# wakeel125.net
KiCad netlist of a schematic drawn in EAGLE
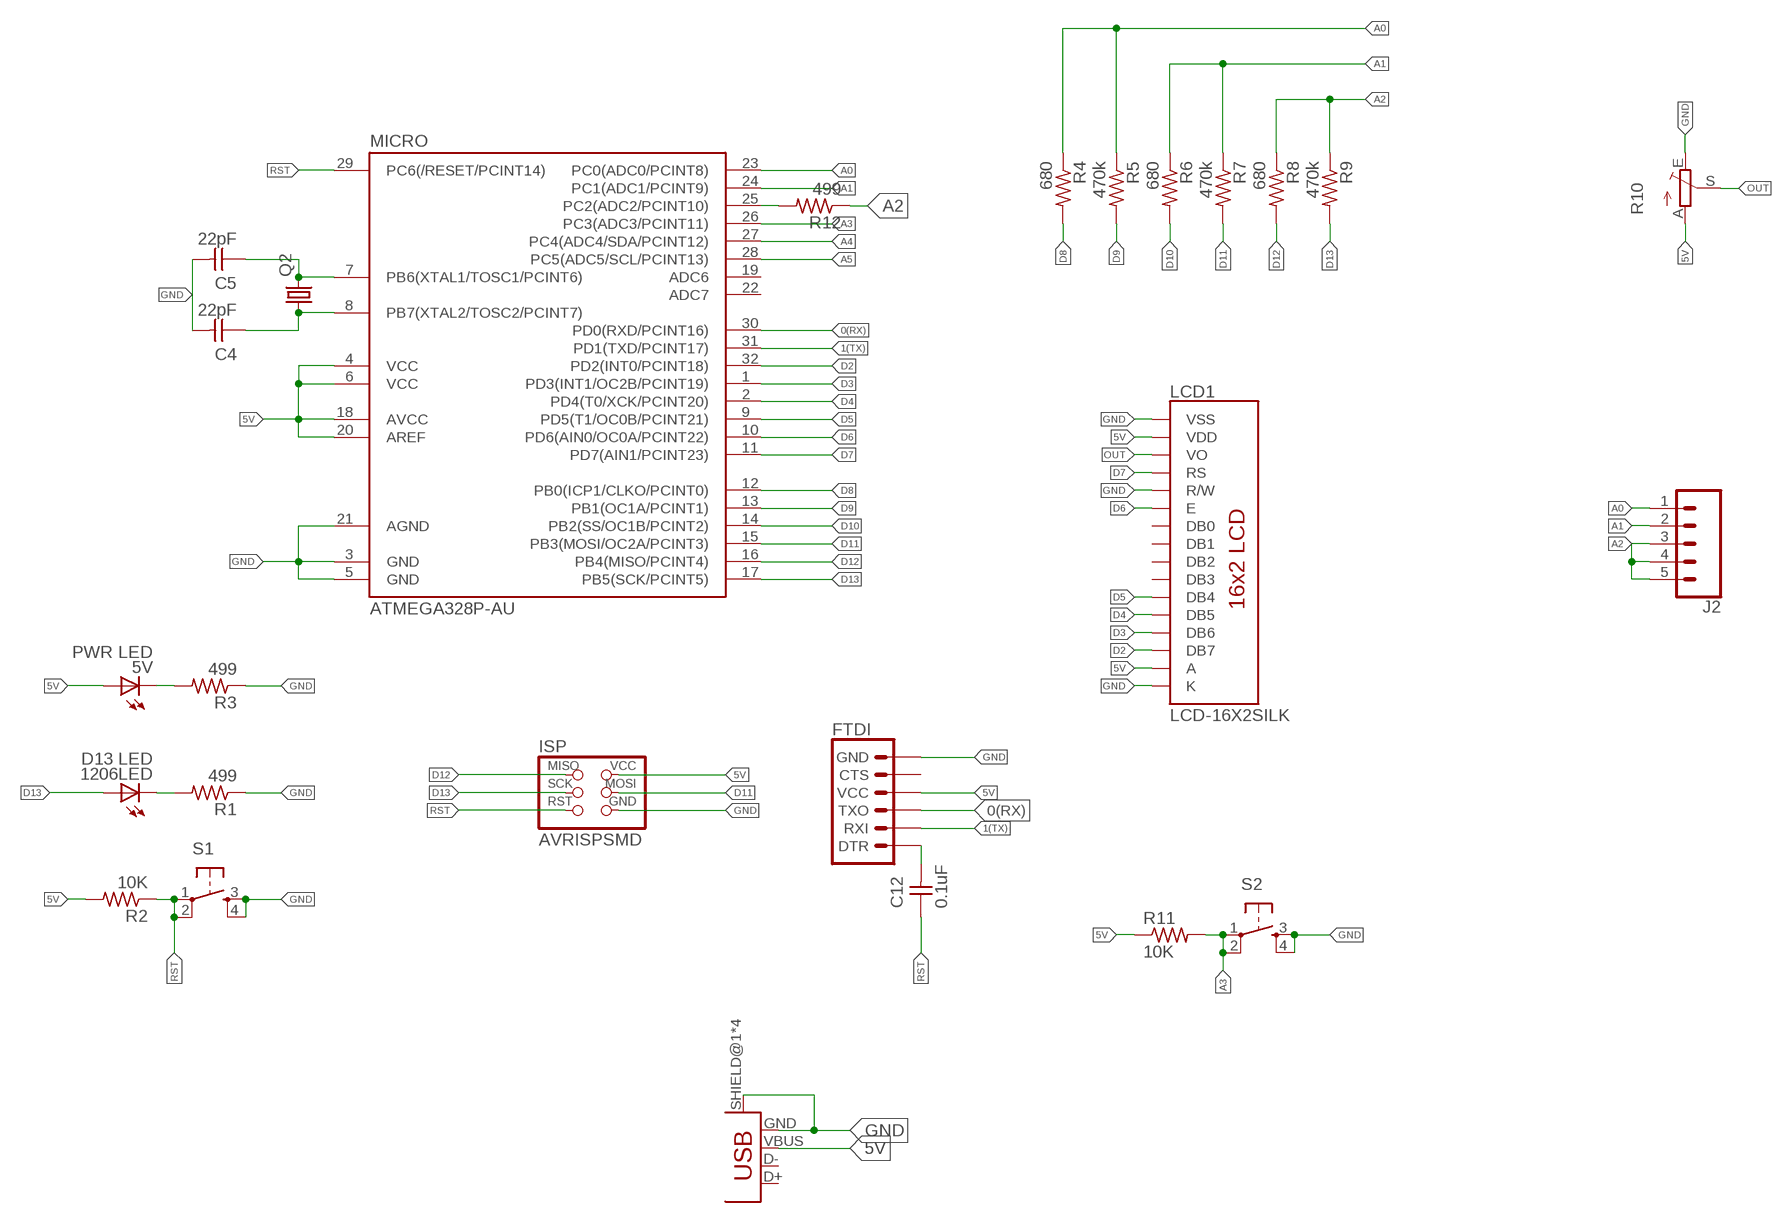
[diagram p0: schematic, sheet 1]

(export (version "E")
  (design (tool "Eeschema 10.0.6"))
  (components
    (comp (ref "5V")
      (value "PWR LED")
      (footprint "eagle-import:LED1206FAB")
      (libsource (lib "eagle-import") (part "LEDFAB1206"))
    )
    (comp (ref "1206LED")
      (value "D13 LED")
      (footprint "eagle-import:LED1206FAB")
      (libsource (lib "eagle-import") (part "LEDFAB1206"))
    )
    (comp (ref "C4")
      (value "22pF")
      (footprint "eagle-import:C1206FAB")
      (libsource (lib "eagle-import") (part "CAP-UNPOLARIZEDFAB"))
    )
    (comp (ref "C5")
      (value "22pF")
      (footprint "eagle-import:C1206FAB")
      (libsource (lib "eagle-import") (part "CAP-UNPOLARIZEDFAB"))
    )
    (comp (ref "C12")
      (value "0.1uF")
      (footprint "eagle-import:C1206FAB")
      (libsource (lib "eagle-import") (part "CAP-UNPOLARIZEDFAB"))
    )
    (comp (ref "CN1")
      (value "USB_MINIB")
      (footprint "eagle-import:USB_MINIB")
      (libsource (lib "eagle-import") (part "USB_MINIB"))
    )
    (comp (ref "FTDI")
      (value "6_PIN_SERIAL_TARGET_SILK")
      (footprint "eagle-import:1X06")
      (libsource (lib "eagle-import") (part "6_PIN_SERIAL_TARGET_SILK"))
    )
    (comp (ref "ISP")
      (value "AVRISPSMD")
      (footprint "eagle-import:2X03SMD")
      (libsource (lib "eagle-import") (part "AVRISPSMD"))
    )
    (comp (ref "J2")
      (value "CONN_05")
      (footprint "eagle-import:1X05")
      (libsource (lib "eagle-import") (part "CONN_05"))
    )
    (comp (ref "LCD1")
      (value "LCD-16X2SILK")
      (footprint "eagle-import:LCD-16X2")
      (libsource (lib "eagle-import") (part "LCD-16X2SILK"))
    )
    (comp (ref "MICRO")
      (value "ATMEGA328P-AU")
      (footprint "eagle-import:TQFP32-08")
      (libsource (lib "eagle-import") (part "ATMEGA48/88/168-AU"))
    )
    (comp (ref "Q2")
      (value "CRYSTALHC49U70")
      (footprint "eagle-import:HC49U70")
      (libsource (lib "eagle-import") (part "CRYSTALHC49U70"))
    )
    (comp (ref "R1")
      (value "499")
      (footprint "eagle-import:R1206FAB")
      (libsource (lib "eagle-import") (part "RES-US1206FAB"))
    )
    (comp (ref "R2")
      (value "10K")
      (footprint "eagle-import:R1206FAB")
      (libsource (lib "eagle-import") (part "RES-US1206FAB"))
    )
    (comp (ref "R3")
      (value "499")
      (footprint "eagle-import:R1206FAB")
      (libsource (lib "eagle-import") (part "RES-US1206FAB"))
    )
    (comp (ref "R4")
      (value "680")
      (footprint "eagle-import:R1206FAB")
      (libsource (lib "eagle-import") (part "RES-US1206FAB"))
    )
    (comp (ref "R5")
      (value "470k")
      (footprint "eagle-import:R1206FAB")
      (libsource (lib "eagle-import") (part "RES-US1206FAB"))
    )
    (comp (ref "R6")
      (value "680")
      (footprint "eagle-import:R1206FAB")
      (libsource (lib "eagle-import") (part "RES-US1206FAB"))
    )
    (comp (ref "R7")
      (value "470k")
      (footprint "eagle-import:R1206FAB")
      (libsource (lib "eagle-import") (part "RES-US1206FAB"))
    )
    (comp (ref "R8")
      (value "680")
      (footprint "eagle-import:R1206FAB")
      (libsource (lib "eagle-import") (part "RES-US1206FAB"))
    )
    (comp (ref "R9")
      (value "470k")
      (footprint "eagle-import:R1206FAB")
      (libsource (lib "eagle-import") (part "RES-US1206FAB"))
    )
    (comp (ref "R10")
      (value "TRIM_EU-B64W")
      (footprint "eagle-import:B64W")
      (libsource (lib "eagle-import") (part "TRIM_EU-B64W"))
    )
    (comp (ref "R11")
      (value "10K")
      (footprint "eagle-import:R1206FAB")
      (libsource (lib "eagle-import") (part "RES-US1206FAB"))
    )
    (comp (ref "R12")
      (value "499")
      (footprint "eagle-import:R1206FAB")
      (libsource (lib "eagle-import") (part "RES-US1206FAB"))
    )
    (comp (ref "S1")
      (value "6MM_SWITCH6MM_SWITCH")
      (footprint "eagle-import:6MM_SWITCH")
      (libsource (lib "eagle-import") (part "6MM_SWITCH6MM_SWITCH"))
    )
    (comp (ref "S2")
      (value "6MM_SWITCH6MM_SWITCH")
      (footprint "eagle-import:6MM_SWITCH")
      (libsource (lib "eagle-import") (part "6MM_SWITCH6MM_SWITCH"))
    )
  )
  (nets
    (net (code "1") (name "0(RX)") (class "Default")
      (node (ref "FTDI") (pin "3") (pinfunction "TXO_3") (pintype "passive"))
      (node (ref "MICRO") (pin "30") (pinfunction "PD0(RXD/PCINT16)_30") (pintype "bidirectional"))
    )
    (net (code "2") (name "1(TX)") (class "Default")
      (node (ref "FTDI") (pin "2") (pinfunction "RXI_2") (pintype "passive"))
      (node (ref "MICRO") (pin "31") (pinfunction "PD1(TXD/PCINT17)_31") (pintype "bidirectional"))
    )
    (net (code "3") (name "5V") (class "Default")
      (node (ref "5V") (pin "1") (pinfunction "A_1") (pintype "passive"))
      (node (ref "CN1") (pin "VBUS") (pinfunction "VBUS_VBUS") (pintype "bidirectional"))
      (node (ref "FTDI") (pin "4") (pinfunction "VCC_4") (pintype "passive"))
      (node (ref "ISP") (pin "2") (pinfunction "VCC_2") (pintype "passive"))
      (node (ref "LCD1") (pin "15") (pinfunction "A_15") (pintype "power_in"))
      (node (ref "LCD1") (pin "2") (pinfunction "VDD_2") (pintype "power_in"))
      (node (ref "MICRO") (pin "18") (pinfunction "AVCC_18") (pintype "passive"))
      (node (ref "MICRO") (pin "20") (pinfunction "AREF_20") (pintype "passive"))
      (node (ref "MICRO") (pin "4") (pinfunction "VCC_4") (pintype "power_in"))
      (node (ref "MICRO") (pin "6") (pinfunction "VCC_6") (pintype "power_in"))
      (node (ref "R10") (pin "A") (pinfunction "A_A") (pintype "passive"))
      (node (ref "R11") (pin "1") (pinfunction "1_1") (pintype "passive"))
      (node (ref "R2") (pin "2") (pinfunction "2_2") (pintype "passive"))
    )
    (net (code "4") (name "A0") (class "Default")
      (node (ref "J2") (pin "1") (pinfunction "1_1") (pintype "passive"))
      (node (ref "MICRO") (pin "23") (pinfunction "PC0(ADC0/PCINT8)_23") (pintype "bidirectional"))
      (node (ref "R4") (pin "1") (pinfunction "1_1") (pintype "passive"))
      (node (ref "R5") (pin "1") (pinfunction "1_1") (pintype "passive"))
    )
    (net (code "5") (name "A1") (class "Default")
      (node (ref "J2") (pin "2") (pinfunction "2_2") (pintype "passive"))
      (node (ref "MICRO") (pin "24") (pinfunction "PC1(ADC1/PCINT9)_24") (pintype "bidirectional"))
      (node (ref "R6") (pin "1") (pinfunction "1_1") (pintype "passive"))
      (node (ref "R7") (pin "1") (pinfunction "1_1") (pintype "passive"))
    )
    (net (code "6") (name "A2") (class "Default")
      (node (ref "J2") (pin "3") (pinfunction "3_3") (pintype "passive"))
      (node (ref "J2") (pin "4") (pinfunction "4_4") (pintype "passive"))
      (node (ref "J2") (pin "5") (pinfunction "5_5") (pintype "passive"))
      (node (ref "R12") (pin "1") (pinfunction "1_1") (pintype "passive"))
      (node (ref "R8") (pin "1") (pinfunction "1_1") (pintype "passive"))
      (node (ref "R9") (pin "1") (pinfunction "1_1") (pintype "passive"))
    )
    (net (code "7") (name "A3") (class "Default")
      (node (ref "MICRO") (pin "26") (pinfunction "PC3(ADC3/PCINT11)_26") (pintype "bidirectional"))
      (node (ref "R11") (pin "2") (pinfunction "2_2") (pintype "passive"))
      (node (ref "S2") (pin "1") (pinfunction "P_1") (pintype "passive"))
      (node (ref "S2") (pin "2") (pinfunction "P1_2") (pintype "passive"))
    )
    (net (code "8") (name "A4") (class "Default")
      (node (ref "MICRO") (pin "27") (pinfunction "PC4(ADC4/SDA/PCINT12)_27") (pintype "bidirectional"))
    )
    (net (code "9") (name "A5") (class "Default")
      (node (ref "MICRO") (pin "28") (pinfunction "PC5(ADC5/SCL/PCINT13)_28") (pintype "bidirectional"))
    )
    (net (code "10") (name "D2") (class "Default")
      (node (ref "LCD1") (pin "14") (pinfunction "DB7_14") (pintype "bidirectional"))
      (node (ref "MICRO") (pin "32") (pinfunction "PD2(INT0/PCINT18)_32") (pintype "bidirectional"))
    )
    (net (code "11") (name "D3") (class "Default")
      (node (ref "LCD1") (pin "13") (pinfunction "DB6_13") (pintype "bidirectional"))
      (node (ref "MICRO") (pin "1") (pinfunction "PD3(INT1/OC2B/PCINT19)_1") (pintype "bidirectional"))
    )
    (net (code "12") (name "D4") (class "Default")
      (node (ref "LCD1") (pin "12") (pinfunction "DB5_12") (pintype "bidirectional"))
      (node (ref "MICRO") (pin "2") (pinfunction "PD4(T0/XCK/PCINT20)_2") (pintype "bidirectional"))
    )
    (net (code "13") (name "D5") (class "Default")
      (node (ref "LCD1") (pin "11") (pinfunction "DB4_11") (pintype "bidirectional"))
      (node (ref "MICRO") (pin "9") (pinfunction "PD5(T1/OC0B/PCINT21)_9") (pintype "bidirectional"))
    )
    (net (code "14") (name "D6") (class "Default")
      (node (ref "LCD1") (pin "6") (pinfunction "E_6") (pintype "input"))
      (node (ref "MICRO") (pin "10") (pinfunction "PD6(AIN0/OC0A/PCINT22)_10") (pintype "bidirectional"))
    )
    (net (code "15") (name "D7") (class "Default")
      (node (ref "LCD1") (pin "4") (pinfunction "RS_4") (pintype "input"))
      (node (ref "MICRO") (pin "11") (pinfunction "PD7(AIN1/PCINT23)_11") (pintype "bidirectional"))
    )
    (net (code "16") (name "D8") (class "Default")
      (node (ref "MICRO") (pin "12") (pinfunction "PB0(ICP1/CLKO/PCINT0)_12") (pintype "bidirectional"))
      (node (ref "R4") (pin "2") (pinfunction "2_2") (pintype "passive"))
    )
    (net (code "17") (name "D9") (class "Default")
      (node (ref "MICRO") (pin "13") (pinfunction "PB1(OC1A/PCINT1)_13") (pintype "bidirectional"))
      (node (ref "R5") (pin "2") (pinfunction "2_2") (pintype "passive"))
    )
    (net (code "18") (name "D10") (class "Default")
      (node (ref "MICRO") (pin "14") (pinfunction "PB2(SS/OC1B/PCINT2)_14") (pintype "bidirectional"))
      (node (ref "R6") (pin "2") (pinfunction "2_2") (pintype "passive"))
    )
    (net (code "19") (name "D11") (class "Default")
      (node (ref "ISP") (pin "4") (pinfunction "MOSI_4") (pintype "passive"))
      (node (ref "MICRO") (pin "15") (pinfunction "PB3(MOSI/OC2A/PCINT3)_15") (pintype "bidirectional"))
      (node (ref "R7") (pin "2") (pinfunction "2_2") (pintype "passive"))
    )
    (net (code "20") (name "D12") (class "Default")
      (node (ref "ISP") (pin "1") (pinfunction "MISO_1") (pintype "passive"))
      (node (ref "MICRO") (pin "16") (pinfunction "PB4(MISO/PCINT4)_16") (pintype "bidirectional"))
      (node (ref "R8") (pin "2") (pinfunction "2_2") (pintype "passive"))
    )
    (net (code "21") (name "D13") (class "Default")
      (node (ref "1206LED") (pin "1") (pinfunction "A_1") (pintype "passive"))
      (node (ref "ISP") (pin "3") (pinfunction "SCK_3") (pintype "passive"))
      (node (ref "MICRO") (pin "17") (pinfunction "PB5(SCK/PCINT5)_17") (pintype "bidirectional"))
      (node (ref "R9") (pin "2") (pinfunction "2_2") (pintype "passive"))
    )
    (net (code "22") (name "GND") (class "Default")
      (node (ref "C4") (pin "2") (pinfunction "2_2") (pintype "passive"))
      (node (ref "C5") (pin "2") (pinfunction "2_2") (pintype "passive"))
      (node (ref "CN1") (pin "GND") (pinfunction "GND_GND") (pintype "bidirectional"))
      (node (ref "CN1") (pin "SHIELD@1") (pinfunction "SHIELD_SHIELD@1") (pintype "passive"))
      (node (ref "CN1") (pin "SHIELD@2") (pinfunction "SHIELD_SHIELD@2") (pintype "passive"))
      (node (ref "CN1") (pin "SHIELD@3") (pinfunction "SHIELD_SHIELD@3") (pintype "passive"))
      (node (ref "CN1") (pin "SHIELD@4") (pinfunction "SHIELD_SHIELD@4") (pintype "passive"))
      (node (ref "FTDI") (pin "6") (pinfunction "GND_6") (pintype "passive"))
      (node (ref "ISP") (pin "6") (pinfunction "GND_6") (pintype "passive"))
      (node (ref "LCD1") (pin "1") (pinfunction "VSS_1") (pintype "power_in"))
      (node (ref "LCD1") (pin "16") (pinfunction "K_16") (pintype "power_in"))
      (node (ref "LCD1") (pin "5") (pinfunction "R/W_5") (pintype "input"))
      (node (ref "MICRO") (pin "21") (pinfunction "AGND_21") (pintype "power_in"))
      (node (ref "MICRO") (pin "3") (pinfunction "GND_3") (pintype "power_in"))
      (node (ref "MICRO") (pin "5") (pinfunction "GND_5") (pintype "power_in"))
      (node (ref "R1") (pin "1") (pinfunction "1_1") (pintype "passive"))
      (node (ref "R10") (pin "E") (pinfunction "E_E") (pintype "passive"))
      (node (ref "R3") (pin "1") (pinfunction "1_1") (pintype "passive"))
      (node (ref "S1") (pin "3") (pinfunction "S_3") (pintype "passive"))
      (node (ref "S1") (pin "4") (pinfunction "S1_4") (pintype "passive"))
      (node (ref "S2") (pin "3") (pinfunction "S_3") (pintype "passive"))
      (node (ref "S2") (pin "4") (pinfunction "S1_4") (pintype "passive"))
    )
    (net (code "23") (name "Net-(5V-C)") (class "Default")
      (node (ref "5V") (pin "2") (pinfunction "C_2") (pintype "passive"))
      (node (ref "R3") (pin "2") (pinfunction "2_2") (pintype "passive"))
    )
    (net (code "24") (name "Net-(1206LED-C)") (class "Default")
      (node (ref "1206LED") (pin "2") (pinfunction "C_2") (pintype "passive"))
      (node (ref "R1") (pin "2") (pinfunction "2_2") (pintype "passive"))
    )
    (net (code "25") (name "Net-(FTDI-DTR)") (class "Default")
      (node (ref "C12") (pin "2") (pinfunction "2_2") (pintype "passive"))
      (node (ref "FTDI") (pin "1") (pinfunction "DTR_1") (pintype "passive"))
    )
    (net (code "26") (name "Net-(MICRO-PB6(XTAL1{slash}TOSC1{slash}PCINT6))") (class "Default")
      (node (ref "C5") (pin "1") (pinfunction "1_1") (pintype "passive"))
      (node (ref "MICRO") (pin "7") (pinfunction "PB6(XTAL1/TOSC1/PCINT6)_7") (pintype "bidirectional"))
      (node (ref "Q2") (pin "2") (pinfunction "2_2") (pintype "passive"))
    )
    (net (code "27") (name "Net-(MICRO-PB7(XTAL2{slash}TOSC2{slash}PCINT7))") (class "Default")
      (node (ref "C4") (pin "1") (pinfunction "1_1") (pintype "passive"))
      (node (ref "MICRO") (pin "8") (pinfunction "PB7(XTAL2/TOSC2/PCINT7)_8") (pintype "bidirectional"))
      (node (ref "Q2") (pin "1") (pinfunction "1_1") (pintype "passive"))
    )
    (net (code "28") (name "Net-(MICRO-PC2(ADC2{slash}PCINT10))") (class "Default")
      (node (ref "MICRO") (pin "25") (pinfunction "PC2(ADC2/PCINT10)_25") (pintype "bidirectional"))
      (node (ref "R12") (pin "2") (pinfunction "2_2") (pintype "passive"))
    )
    (net (code "29") (name "OUT") (class "Default")
      (node (ref "LCD1") (pin "3") (pinfunction "VO_3") (pintype "bidirectional"))
      (node (ref "R10") (pin "S") (pinfunction "S_S") (pintype "passive"))
    )
    (net (code "30") (name "RST") (class "Default")
      (node (ref "C12") (pin "1") (pinfunction "1_1") (pintype "passive"))
      (node (ref "ISP") (pin "5") (pinfunction "RST_5") (pintype "passive"))
      (node (ref "MICRO") (pin "29") (pinfunction "PC6(/RESET/PCINT14)_29") (pintype "bidirectional"))
      (node (ref "R2") (pin "1") (pinfunction "1_1") (pintype "passive"))
      (node (ref "S1") (pin "1") (pinfunction "P_1") (pintype "passive"))
      (node (ref "S1") (pin "2") (pinfunction "P1_2") (pintype "passive"))
    )
    (net (code "31") (name "unconnected-(CN1-PadD+)") (class "Default")
      (node (ref "CN1") (pin "D+") (pinfunction "D+_D+") (pintype "bidirectional"))
    )
    (net (code "32") (name "unconnected-(CN1-PadD-)") (class "Default")
      (node (ref "CN1") (pin "D-") (pinfunction "D-_D-") (pintype "bidirectional"))
    )
    (net (code "33") (name "unconnected-(FTDI-CTS-Pad5)") (class "Default")
      (node (ref "FTDI") (pin "5") (pinfunction "CTS_5") (pintype "passive"))
    )
    (net (code "34") (name "unconnected-(LCD1-DB0-Pad7)") (class "Default")
      (node (ref "LCD1") (pin "7") (pinfunction "DB0_7") (pintype "bidirectional"))
    )
    (net (code "35") (name "unconnected-(LCD1-DB1-Pad8)") (class "Default")
      (node (ref "LCD1") (pin "8") (pinfunction "DB1_8") (pintype "bidirectional"))
    )
    (net (code "36") (name "unconnected-(LCD1-DB2-Pad9)") (class "Default")
      (node (ref "LCD1") (pin "9") (pinfunction "DB2_9") (pintype "bidirectional"))
    )
    (net (code "37") (name "unconnected-(LCD1-DB3-Pad10)") (class "Default")
      (node (ref "LCD1") (pin "10") (pinfunction "DB3_10") (pintype "bidirectional"))
    )
    (net (code "38") (name "unconnected-(MICRO-ADC6-Pad19)") (class "Default")
      (node (ref "MICRO") (pin "19") (pinfunction "ADC6_19") (pintype "passive"))
    )
    (net (code "39") (name "unconnected-(MICRO-ADC7-Pad22)") (class "Default")
      (node (ref "MICRO") (pin "22") (pinfunction "ADC7_22") (pintype "passive"))
    )
  )
)
